# USBdimmer-control-noxfmr.net
KiCad netlist of a schematic drawn in EAGLE
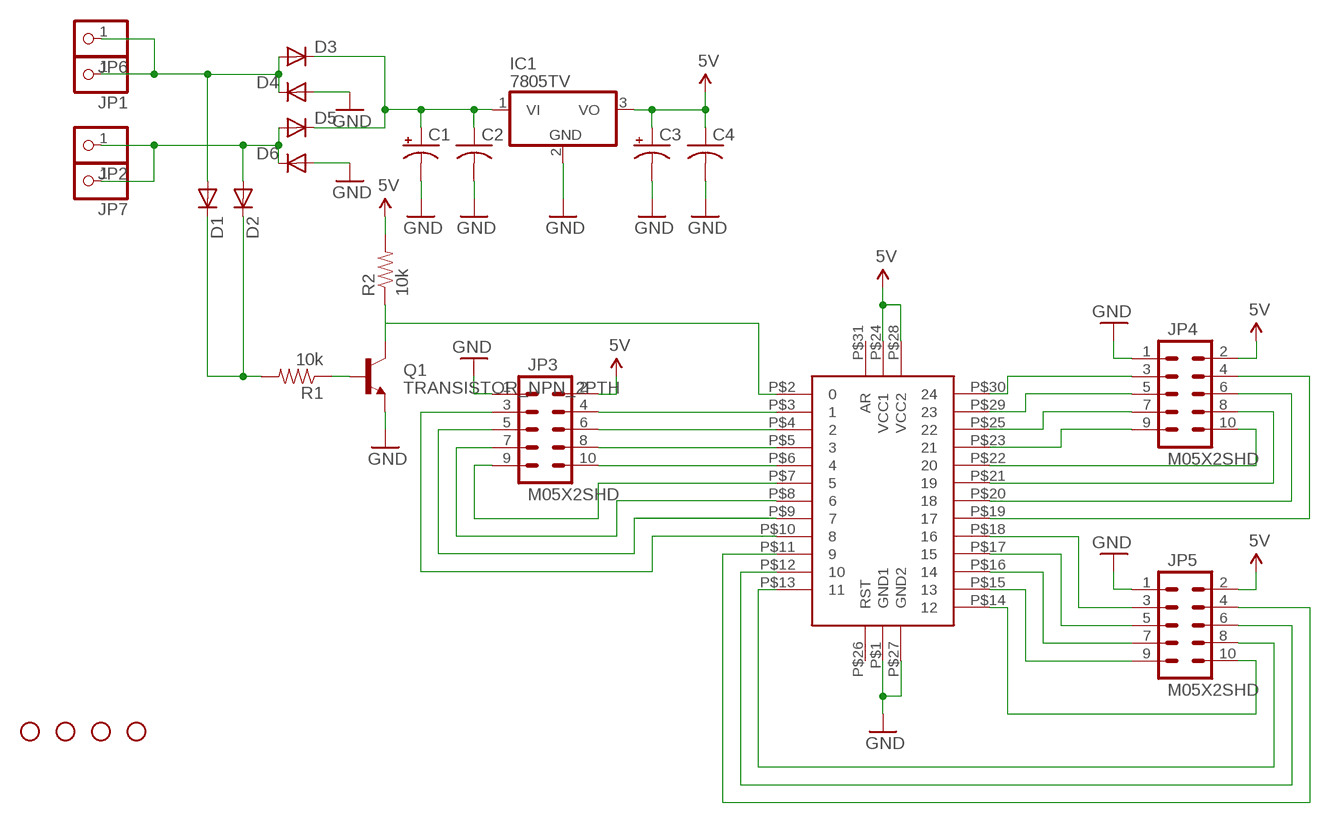
[diagram p0: schematic, sheet 1]

(export (version "E")
  (design (tool "Eeschema 10.0.6"))
  (components
    (comp (ref "C1")
      (value "CPOL-USE3.5-10")
      (footprint "eagle-import:E3,5-10")
      (libsource (lib "eagle-import") (part "CPOL-USE3.5-10"))
    )
    (comp (ref "C2")
      (value "C-US025-030X050")
      (footprint "eagle-import:C025-030X050")
      (libsource (lib "eagle-import") (part "C-US025-030X050"))
    )
    (comp (ref "C3")
      (value "CPOL-USE3.5-10")
      (footprint "eagle-import:E3,5-10")
      (libsource (lib "eagle-import") (part "CPOL-USE3.5-10"))
    )
    (comp (ref "C4")
      (value "C-US025-030X050")
      (footprint "eagle-import:C025-030X050")
      (libsource (lib "eagle-import") (part "C-US025-030X050"))
    )
    (comp (ref "D1")
      (value "DIODE1N4148")
      (footprint "eagle-import:DIODE-1N4148")
      (libsource (lib "eagle-import") (part "DIODE1N4148"))
    )
    (comp (ref "D2")
      (value "DIODE1N4148")
      (footprint "eagle-import:DIODE-1N4148")
      (libsource (lib "eagle-import") (part "DIODE1N4148"))
    )
    (comp (ref "D3")
      (value "DIODEPTH")
      (footprint "eagle-import:DIODE-1N4001")
      (libsource (lib "eagle-import") (part "DIODEPTH"))
    )
    (comp (ref "D4")
      (value "DIODEPTH")
      (footprint "eagle-import:DIODE-1N4001")
      (libsource (lib "eagle-import") (part "DIODEPTH"))
    )
    (comp (ref "D5")
      (value "DIODEPTH")
      (footprint "eagle-import:DIODE-1N4001")
      (libsource (lib "eagle-import") (part "DIODEPTH"))
    )
    (comp (ref "D6")
      (value "DIODEPTH")
      (footprint "eagle-import:DIODE-1N4001")
      (libsource (lib "eagle-import") (part "DIODEPTH"))
    )
    (comp (ref "IC1")
      (value "7805TV")
      (footprint "eagle-import:TO220V")
      (libsource (lib "eagle-import") (part "78TV05"))
    )
    (comp (ref "IC2")
      (value "TEENSY2")
      (footprint "eagle-import:TEENSY2")
      (libsource (lib "eagle-import") (part "TEENSY2"))
    )
    (comp (ref "JP1")
      (value "PINHD-1X1")
      (footprint "eagle-import:1X01")
      (libsource (lib "eagle-import") (part "PINHD-1X1"))
    )
    (comp (ref "JP2")
      (value "PINHD-1X1")
      (footprint "eagle-import:1X01")
      (libsource (lib "eagle-import") (part "PINHD-1X1"))
    )
    (comp (ref "JP3")
      (value "M05X2SHD")
      (footprint "eagle-import:2X5-SHROUDED")
      (libsource (lib "eagle-import") (part "M05X2SHD"))
    )
    (comp (ref "JP4")
      (value "M05X2SHD")
      (footprint "eagle-import:2X5-SHROUDED")
      (libsource (lib "eagle-import") (part "M05X2SHD"))
    )
    (comp (ref "JP5")
      (value "M05X2SHD")
      (footprint "eagle-import:2X5-SHROUDED")
      (libsource (lib "eagle-import") (part "M05X2SHD"))
    )
    (comp (ref "JP6")
      (value "PINHD-1X1")
      (footprint "eagle-import:1X01")
      (libsource (lib "eagle-import") (part "PINHD-1X1"))
    )
    (comp (ref "JP7")
      (value "PINHD-1X1")
      (footprint "eagle-import:1X01")
      (libsource (lib "eagle-import") (part "PINHD-1X1"))
    )
    (comp (ref "Q1")
      (value "TRANSISTOR_NPN_2PTH")
      (footprint "eagle-import:TO-92")
      (libsource (lib "eagle-import") (part "TRANSISTOR_NPN_2PTH"))
    )
    (comp (ref "R1")
      (value "10k")
      (footprint "eagle-import:AXIAL-0.4")
      (libsource (lib "eagle-import") (part "RESISTORPTH-1/4W"))
    )
    (comp (ref "R2")
      (value "10k")
      (footprint "eagle-import:AXIAL-0.4")
      (libsource (lib "eagle-import") (part "RESISTORPTH-1/4W"))
    )
    (comp (ref "STANDOFF1")
      (value "STAND-OFF")
      (footprint "eagle-import:STAND-OFF")
      (libsource (lib "eagle-import") (part "STAND-OFF"))
    )
    (comp (ref "STANDOFF2")
      (value "STAND-OFF")
      (footprint "eagle-import:STAND-OFF")
      (libsource (lib "eagle-import") (part "STAND-OFF"))
    )
    (comp (ref "STANDOFF3")
      (value "STAND-OFF")
      (footprint "eagle-import:STAND-OFF")
      (libsource (lib "eagle-import") (part "STAND-OFF"))
    )
    (comp (ref "STANDOFF4")
      (value "STAND-OFF")
      (footprint "eagle-import:STAND-OFF")
      (libsource (lib "eagle-import") (part "STAND-OFF"))
    )
  )
  (nets
    (net (code "1") (name "5V") (class "Default")
      (node (ref "C3") (pin "+") (pinfunction "+_+") (pintype "passive"))
      (node (ref "C4") (pin "1") (pinfunction "1_1") (pintype "passive"))
      (node (ref "IC1") (pin "3") (pinfunction "VO_3") (pintype "passive"))
      (node (ref "IC2") (pin "P$24") (pinfunction "VCC1_P$24") (pintype "bidirectional"))
      (node (ref "IC2") (pin "P$28") (pinfunction "VCC2_P$28") (pintype "bidirectional"))
      (node (ref "JP3") (pin "2") (pinfunction "2_2") (pintype "passive"))
      (node (ref "JP4") (pin "2") (pinfunction "2_2") (pintype "passive"))
      (node (ref "JP5") (pin "2") (pinfunction "2_2") (pintype "passive"))
      (node (ref "R2") (pin "P$2") (pinfunction "2_P$2") (pintype "passive"))
    )
    (net (code "2") (name "GND") (class "Default")
      (node (ref "C1") (pin "-") (pinfunction "-_-") (pintype "passive"))
      (node (ref "C2") (pin "2") (pinfunction "2_2") (pintype "passive"))
      (node (ref "C3") (pin "-") (pinfunction "-_-") (pintype "passive"))
      (node (ref "C4") (pin "2") (pinfunction "2_2") (pintype "passive"))
      (node (ref "D4") (pin "A") (pinfunction "A_A") (pintype "passive"))
      (node (ref "D6") (pin "A") (pinfunction "A_A") (pintype "passive"))
      (node (ref "IC1") (pin "2") (pinfunction "GND_2") (pintype "passive"))
      (node (ref "IC2") (pin "P$1") (pinfunction "GND1_P$1") (pintype "bidirectional"))
      (node (ref "IC2") (pin "P$27") (pinfunction "GND2_P$27") (pintype "bidirectional"))
      (node (ref "JP3") (pin "1") (pinfunction "1_1") (pintype "passive"))
      (node (ref "JP4") (pin "1") (pinfunction "1_1") (pintype "passive"))
      (node (ref "JP5") (pin "1") (pinfunction "1_1") (pintype "passive"))
      (node (ref "Q1") (pin "3") (pinfunction "E_3") (pintype "passive"))
    )
    (net (code "3") (name "Net-(D1-PadA)") (class "Default")
      (node (ref "D1") (pin "A") (pinfunction "A_A") (pintype "passive"))
      (node (ref "D3") (pin "A") (pinfunction "A_A") (pintype "passive"))
      (node (ref "D4") (pin "C") (pinfunction "C_C") (pintype "passive"))
      (node (ref "JP1") (pin "1") (pinfunction "1_1") (pintype "passive"))
      (node (ref "JP6") (pin "1") (pinfunction "1_1") (pintype "passive"))
    )
    (net (code "4") (name "Net-(D2-PadA)") (class "Default")
      (node (ref "D2") (pin "A") (pinfunction "A_A") (pintype "passive"))
      (node (ref "D5") (pin "A") (pinfunction "A_A") (pintype "passive"))
      (node (ref "D6") (pin "C") (pinfunction "C_C") (pintype "passive"))
      (node (ref "JP2") (pin "1") (pinfunction "1_1") (pintype "passive"))
      (node (ref "JP7") (pin "1") (pinfunction "1_1") (pintype "passive"))
    )
    (net (code "5") (name "Net-(IC1-VI)") (class "Default")
      (node (ref "C1") (pin "+") (pinfunction "+_+") (pintype "passive"))
      (node (ref "C2") (pin "1") (pinfunction "1_1") (pintype "passive"))
      (node (ref "D3") (pin "C") (pinfunction "C_C") (pintype "passive"))
      (node (ref "D5") (pin "C") (pinfunction "C_C") (pintype "passive"))
      (node (ref "IC1") (pin "1") (pinfunction "VI_1") (pintype "input"))
    )
    (net (code "6") (name "Net-(IC2-0)") (class "Default")
      (node (ref "IC2") (pin "P$2") (pinfunction "0_P$2") (pintype "bidirectional"))
      (node (ref "Q1") (pin "1") (pinfunction "C_1") (pintype "passive"))
      (node (ref "R2") (pin "P$1") (pinfunction "1_P$1") (pintype "passive"))
    )
    (net (code "7") (name "Net-(IC2-1)") (class "Default")
      (node (ref "IC2") (pin "P$3") (pinfunction "1_P$3") (pintype "bidirectional"))
      (node (ref "JP3") (pin "4") (pinfunction "4_4") (pintype "passive"))
    )
    (net (code "8") (name "Net-(IC2-2)") (class "Default")
      (node (ref "IC2") (pin "P$4") (pinfunction "2_P$4") (pintype "bidirectional"))
      (node (ref "JP3") (pin "6") (pinfunction "6_6") (pintype "passive"))
    )
    (net (code "9") (name "Net-(IC2-3)") (class "Default")
      (node (ref "IC2") (pin "P$5") (pinfunction "3_P$5") (pintype "bidirectional"))
      (node (ref "JP3") (pin "8") (pinfunction "8_8") (pintype "passive"))
    )
    (net (code "10") (name "Net-(IC2-4)") (class "Default")
      (node (ref "IC2") (pin "P$6") (pinfunction "4_P$6") (pintype "bidirectional"))
      (node (ref "JP3") (pin "10") (pinfunction "10_10") (pintype "passive"))
    )
    (net (code "11") (name "Net-(IC2-5)") (class "Default")
      (node (ref "IC2") (pin "P$7") (pinfunction "5_P$7") (pintype "bidirectional"))
      (node (ref "JP3") (pin "9") (pinfunction "9_9") (pintype "passive"))
    )
    (net (code "12") (name "Net-(IC2-6)") (class "Default")
      (node (ref "IC2") (pin "P$8") (pinfunction "6_P$8") (pintype "bidirectional"))
      (node (ref "JP3") (pin "7") (pinfunction "7_7") (pintype "passive"))
    )
    (net (code "13") (name "Net-(IC2-7)") (class "Default")
      (node (ref "IC2") (pin "P$9") (pinfunction "7_P$9") (pintype "bidirectional"))
      (node (ref "JP3") (pin "5") (pinfunction "5_5") (pintype "passive"))
    )
    (net (code "14") (name "Net-(IC2-8)") (class "Default")
      (node (ref "IC2") (pin "P$10") (pinfunction "8_P$10") (pintype "bidirectional"))
      (node (ref "JP3") (pin "3") (pinfunction "3_3") (pintype "passive"))
    )
    (net (code "15") (name "Net-(IC2-9)") (class "Default")
      (node (ref "IC2") (pin "P$11") (pinfunction "9_P$11") (pintype "bidirectional"))
      (node (ref "JP5") (pin "4") (pinfunction "4_4") (pintype "passive"))
    )
    (net (code "16") (name "Net-(IC2-10)") (class "Default")
      (node (ref "IC2") (pin "P$12") (pinfunction "10_P$12") (pintype "bidirectional"))
      (node (ref "JP5") (pin "6") (pinfunction "6_6") (pintype "passive"))
    )
    (net (code "17") (name "Net-(IC2-11)") (class "Default")
      (node (ref "IC2") (pin "P$13") (pinfunction "11_P$13") (pintype "bidirectional"))
      (node (ref "JP5") (pin "8") (pinfunction "8_8") (pintype "passive"))
    )
    (net (code "18") (name "Net-(IC2-12)") (class "Default")
      (node (ref "IC2") (pin "P$14") (pinfunction "12_P$14") (pintype "bidirectional"))
      (node (ref "JP5") (pin "10") (pinfunction "10_10") (pintype "passive"))
    )
    (net (code "19") (name "Net-(IC2-13)") (class "Default")
      (node (ref "IC2") (pin "P$15") (pinfunction "13_P$15") (pintype "bidirectional"))
      (node (ref "JP5") (pin "9") (pinfunction "9_9") (pintype "passive"))
    )
    (net (code "20") (name "Net-(IC2-14)") (class "Default")
      (node (ref "IC2") (pin "P$16") (pinfunction "14_P$16") (pintype "bidirectional"))
      (node (ref "JP5") (pin "7") (pinfunction "7_7") (pintype "passive"))
    )
    (net (code "21") (name "Net-(IC2-15)") (class "Default")
      (node (ref "IC2") (pin "P$17") (pinfunction "15_P$17") (pintype "bidirectional"))
      (node (ref "JP5") (pin "5") (pinfunction "5_5") (pintype "passive"))
    )
    (net (code "22") (name "Net-(IC2-16)") (class "Default")
      (node (ref "IC2") (pin "P$18") (pinfunction "16_P$18") (pintype "bidirectional"))
      (node (ref "JP5") (pin "3") (pinfunction "3_3") (pintype "passive"))
    )
    (net (code "23") (name "Net-(IC2-17)") (class "Default")
      (node (ref "IC2") (pin "P$19") (pinfunction "17_P$19") (pintype "bidirectional"))
      (node (ref "JP4") (pin "4") (pinfunction "4_4") (pintype "passive"))
    )
    (net (code "24") (name "Net-(IC2-18)") (class "Default")
      (node (ref "IC2") (pin "P$20") (pinfunction "18_P$20") (pintype "bidirectional"))
      (node (ref "JP4") (pin "6") (pinfunction "6_6") (pintype "passive"))
    )
    (net (code "25") (name "Net-(IC2-19)") (class "Default")
      (node (ref "IC2") (pin "P$21") (pinfunction "19_P$21") (pintype "bidirectional"))
      (node (ref "JP4") (pin "8") (pinfunction "8_8") (pintype "passive"))
    )
    (net (code "26") (name "Net-(IC2-20)") (class "Default")
      (node (ref "IC2") (pin "P$22") (pinfunction "20_P$22") (pintype "bidirectional"))
      (node (ref "JP4") (pin "10") (pinfunction "10_10") (pintype "passive"))
    )
    (net (code "27") (name "Net-(IC2-21)") (class "Default")
      (node (ref "IC2") (pin "P$23") (pinfunction "21_P$23") (pintype "bidirectional"))
      (node (ref "JP4") (pin "9") (pinfunction "9_9") (pintype "passive"))
    )
    (net (code "28") (name "Net-(IC2-22)") (class "Default")
      (node (ref "IC2") (pin "P$25") (pinfunction "22_P$25") (pintype "bidirectional"))
      (node (ref "JP4") (pin "7") (pinfunction "7_7") (pintype "passive"))
    )
    (net (code "29") (name "Net-(IC2-23)") (class "Default")
      (node (ref "IC2") (pin "P$29") (pinfunction "23_P$29") (pintype "bidirectional"))
      (node (ref "JP4") (pin "5") (pinfunction "5_5") (pintype "passive"))
    )
    (net (code "30") (name "Net-(IC2-24)") (class "Default")
      (node (ref "IC2") (pin "P$30") (pinfunction "24_P$30") (pintype "bidirectional"))
      (node (ref "JP4") (pin "3") (pinfunction "3_3") (pintype "passive"))
    )
    (net (code "31") (name "Net-(Q1-B)") (class "Default")
      (node (ref "Q1") (pin "2") (pinfunction "B_2") (pintype "passive"))
      (node (ref "R1") (pin "P$1") (pinfunction "1_P$1") (pintype "passive"))
    )
    (net (code "32") (name "Net-(R1-2)") (class "Default")
      (node (ref "D1") (pin "C") (pinfunction "C_C") (pintype "passive"))
      (node (ref "D2") (pin "C") (pinfunction "C_C") (pintype "passive"))
      (node (ref "R1") (pin "P$2") (pinfunction "2_P$2") (pintype "passive"))
    )
    (net (code "33") (name "unconnected-(IC2-AR-PadP$31)") (class "Default")
      (node (ref "IC2") (pin "P$31") (pinfunction "AR_P$31") (pintype "bidirectional"))
    )
    (net (code "34") (name "unconnected-(IC2-RST-PadP$26)") (class "Default")
      (node (ref "IC2") (pin "P$26") (pinfunction "RST_P$26") (pintype "bidirectional"))
    )
  )
)
